# led_board_robot_vs_v2.net
KiCad netlist of a schematic drawn in EAGLE
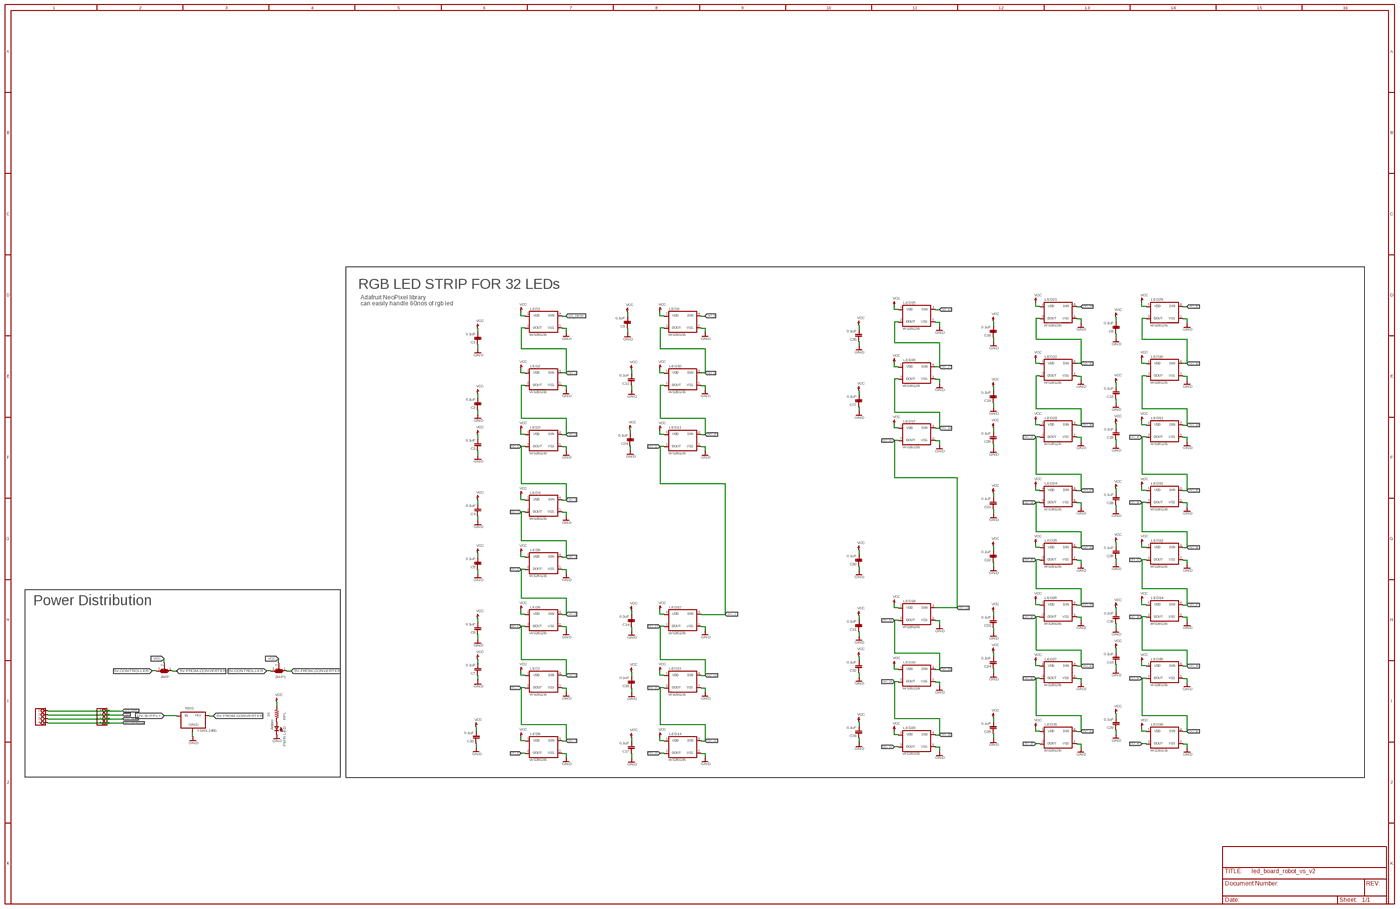
[diagram p0: schematic, sheet 1, overview]
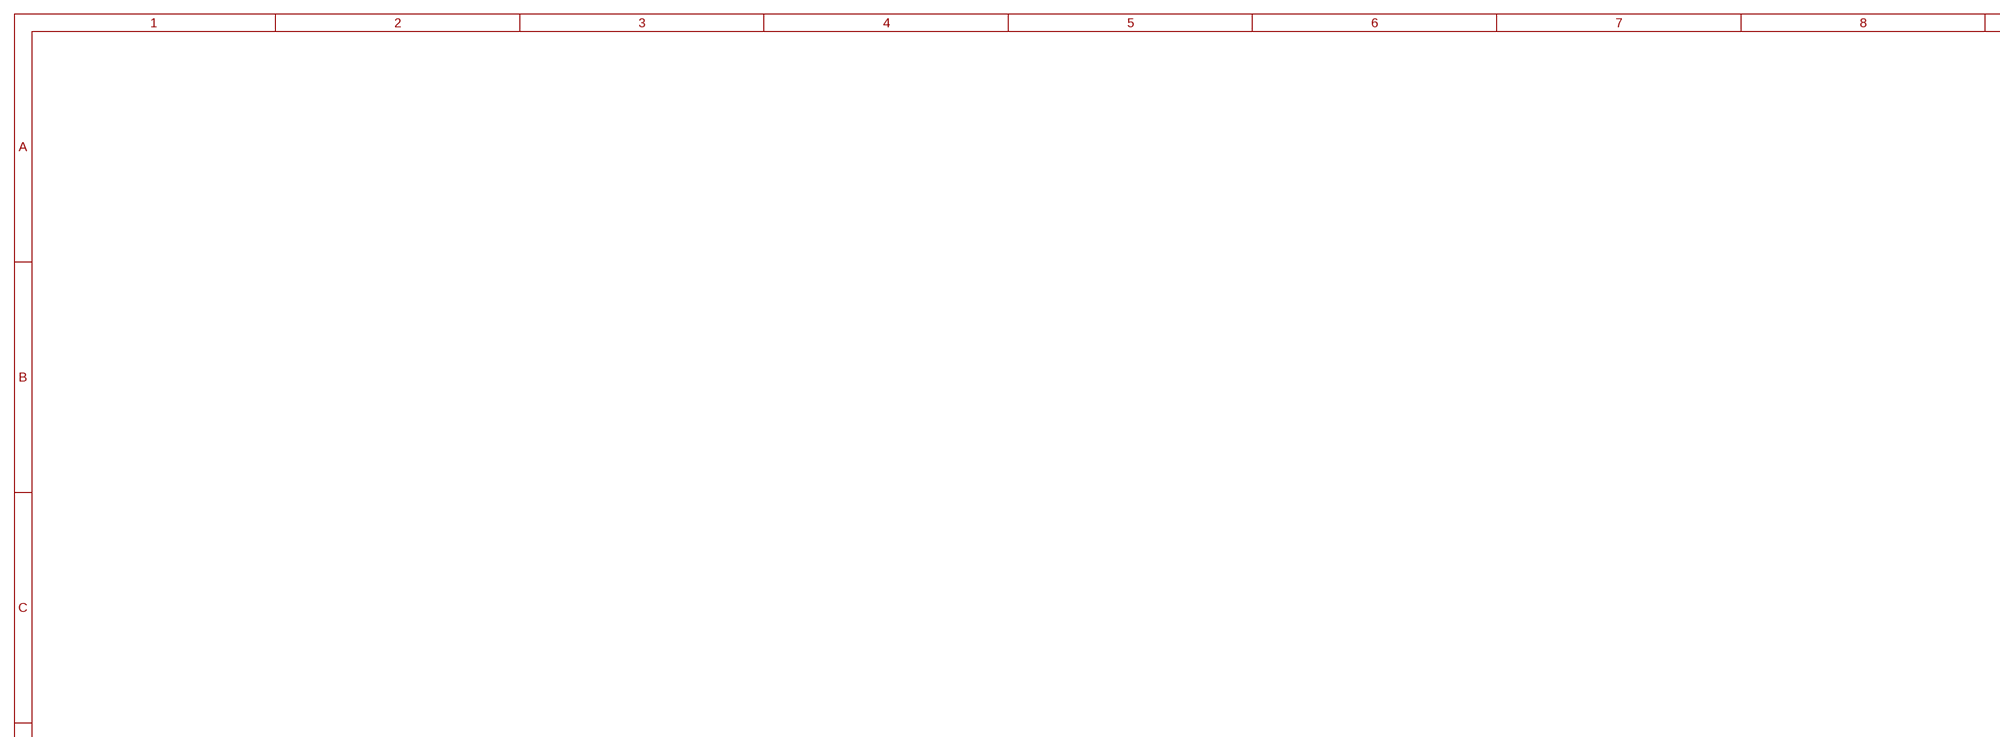
[diagram p1: schematic, sheet 1, part 1 of 4]
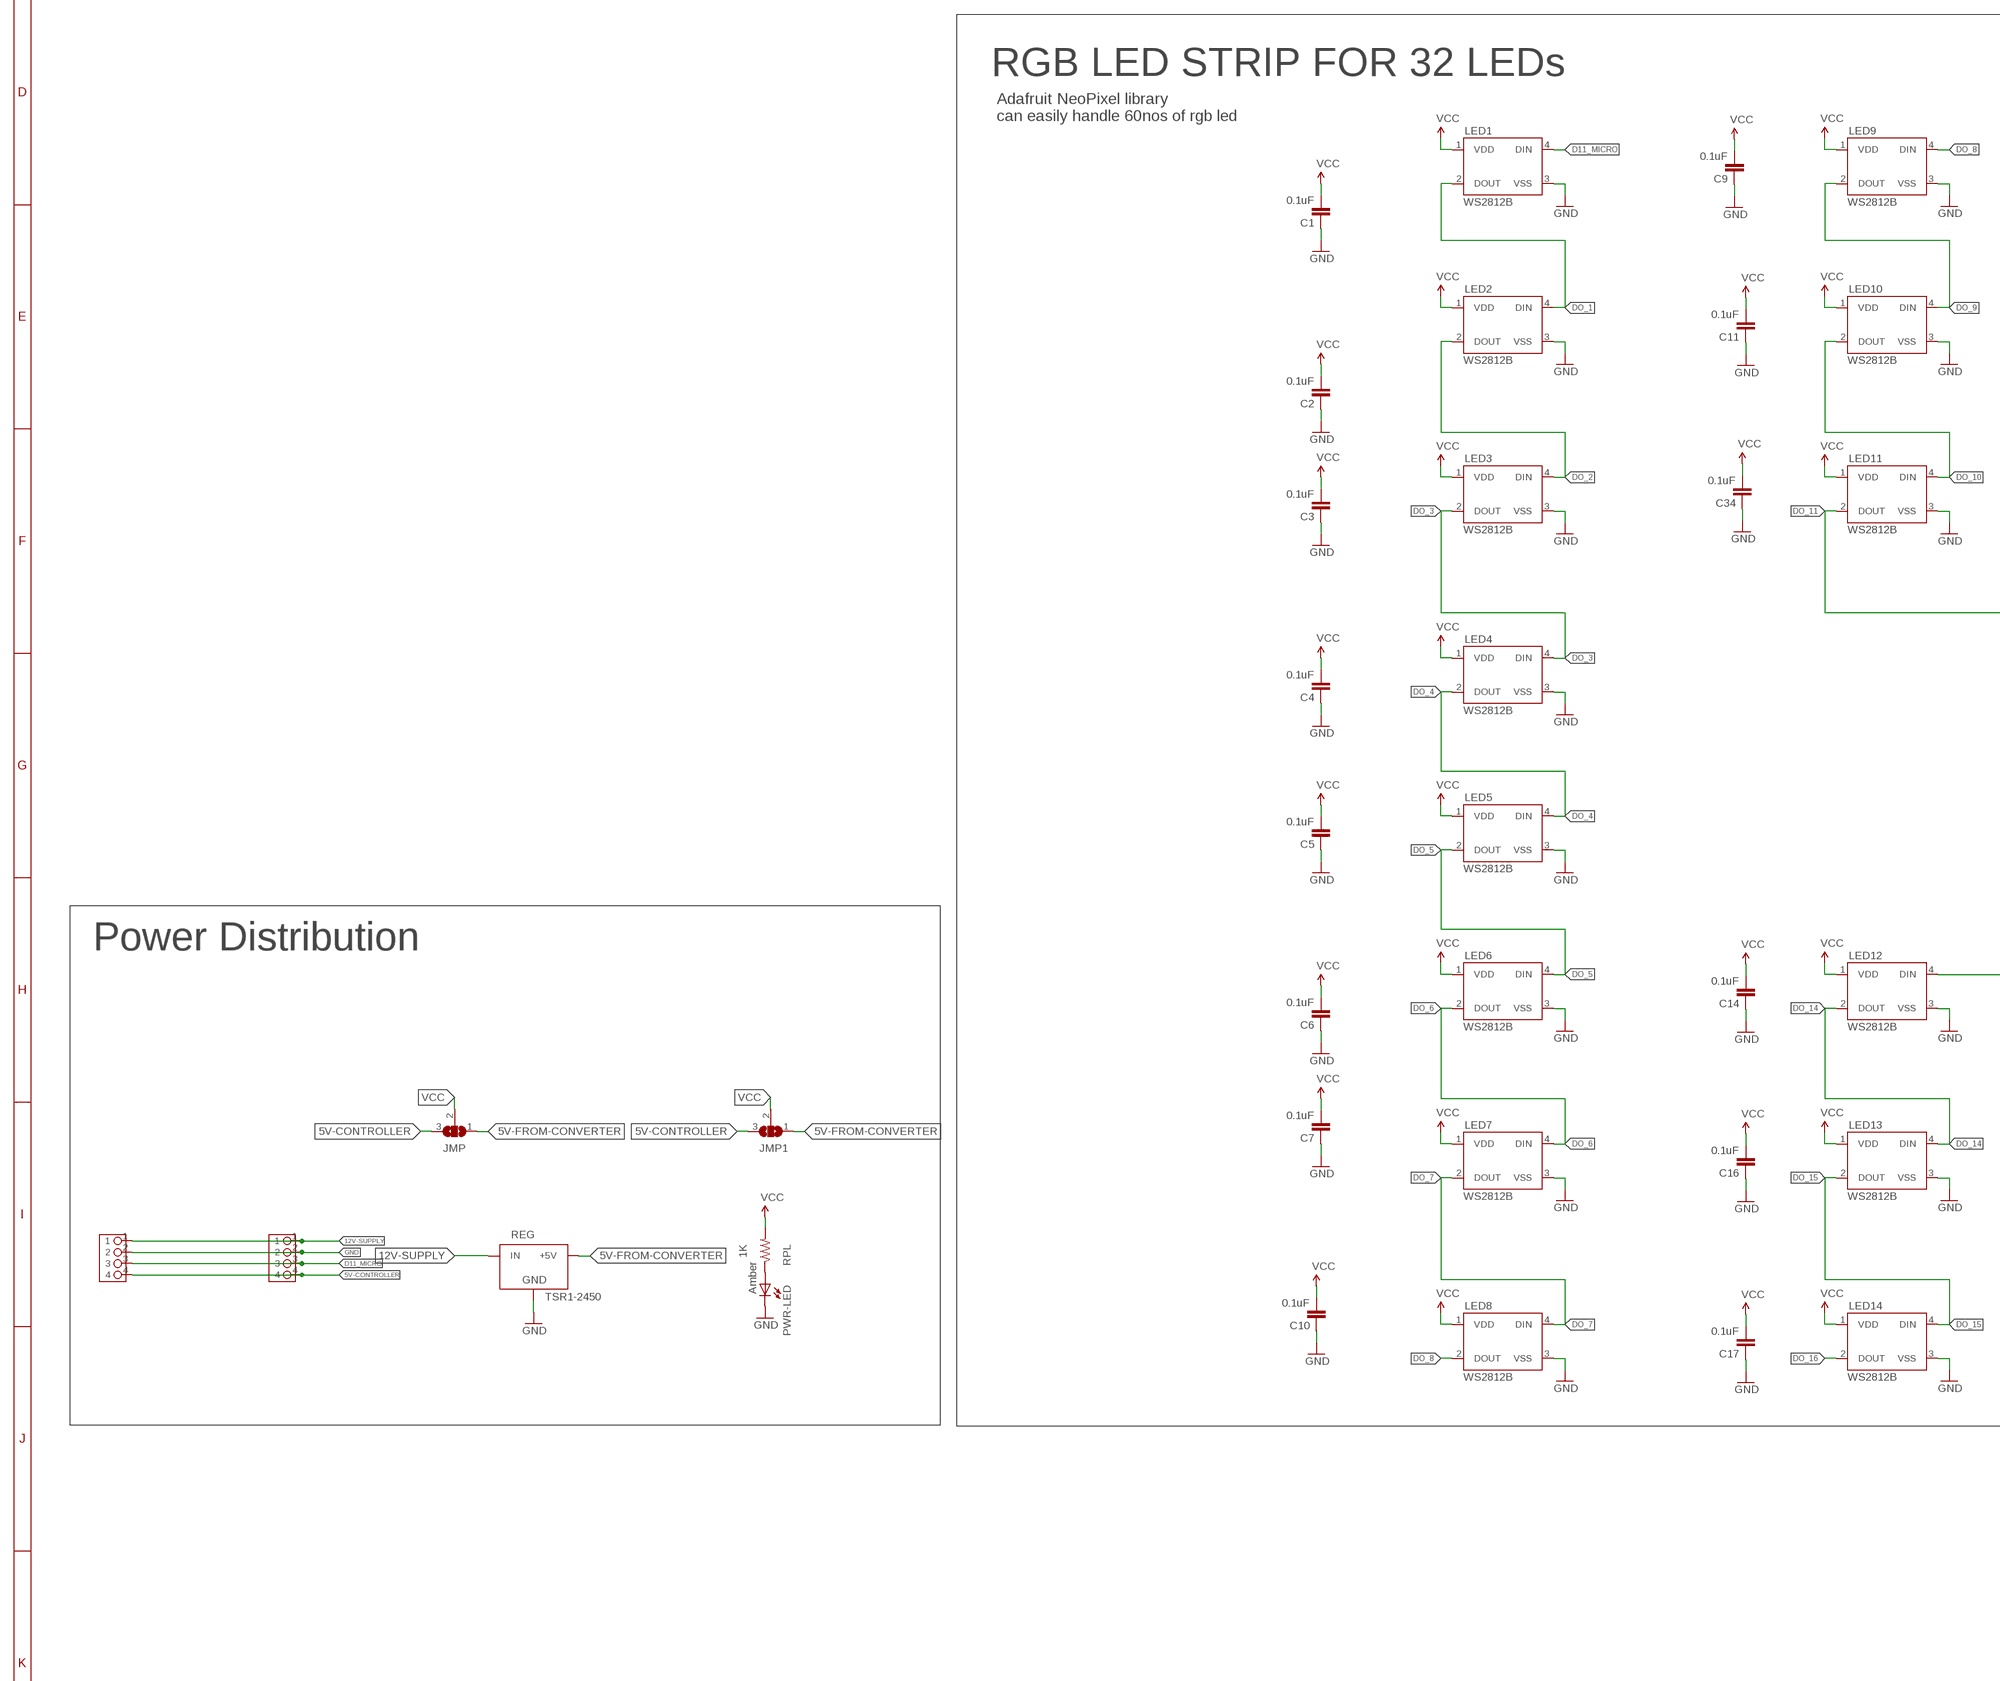
[diagram p2: schematic, sheet 1, part 2 of 4]
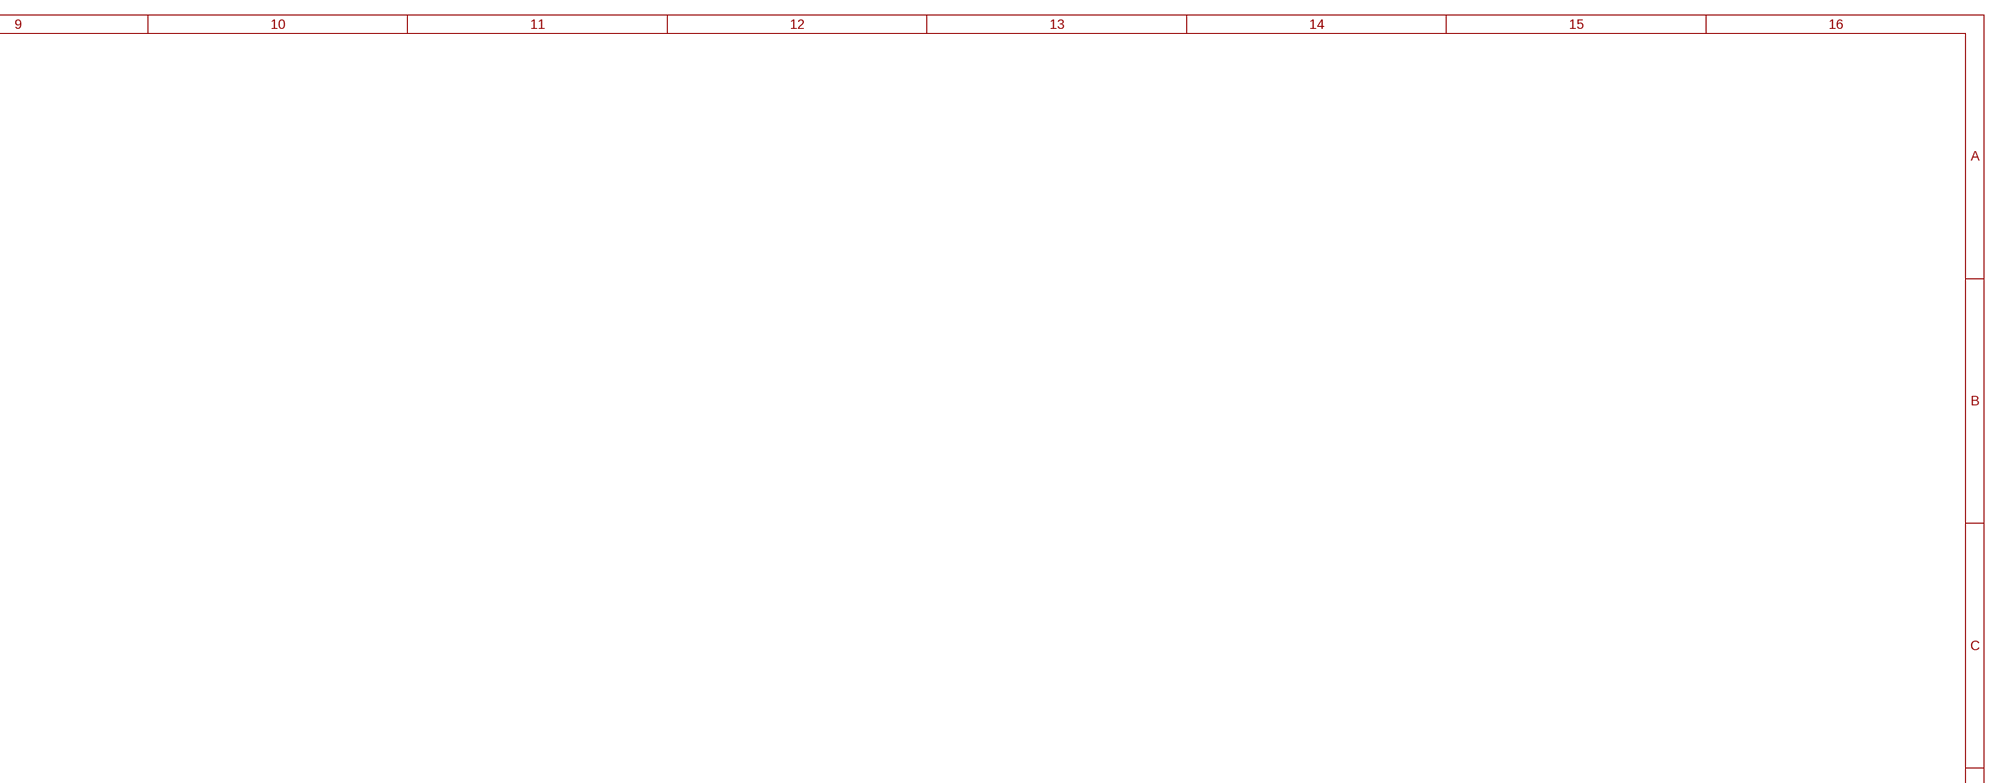
[diagram p3: schematic, sheet 1, part 3 of 4]
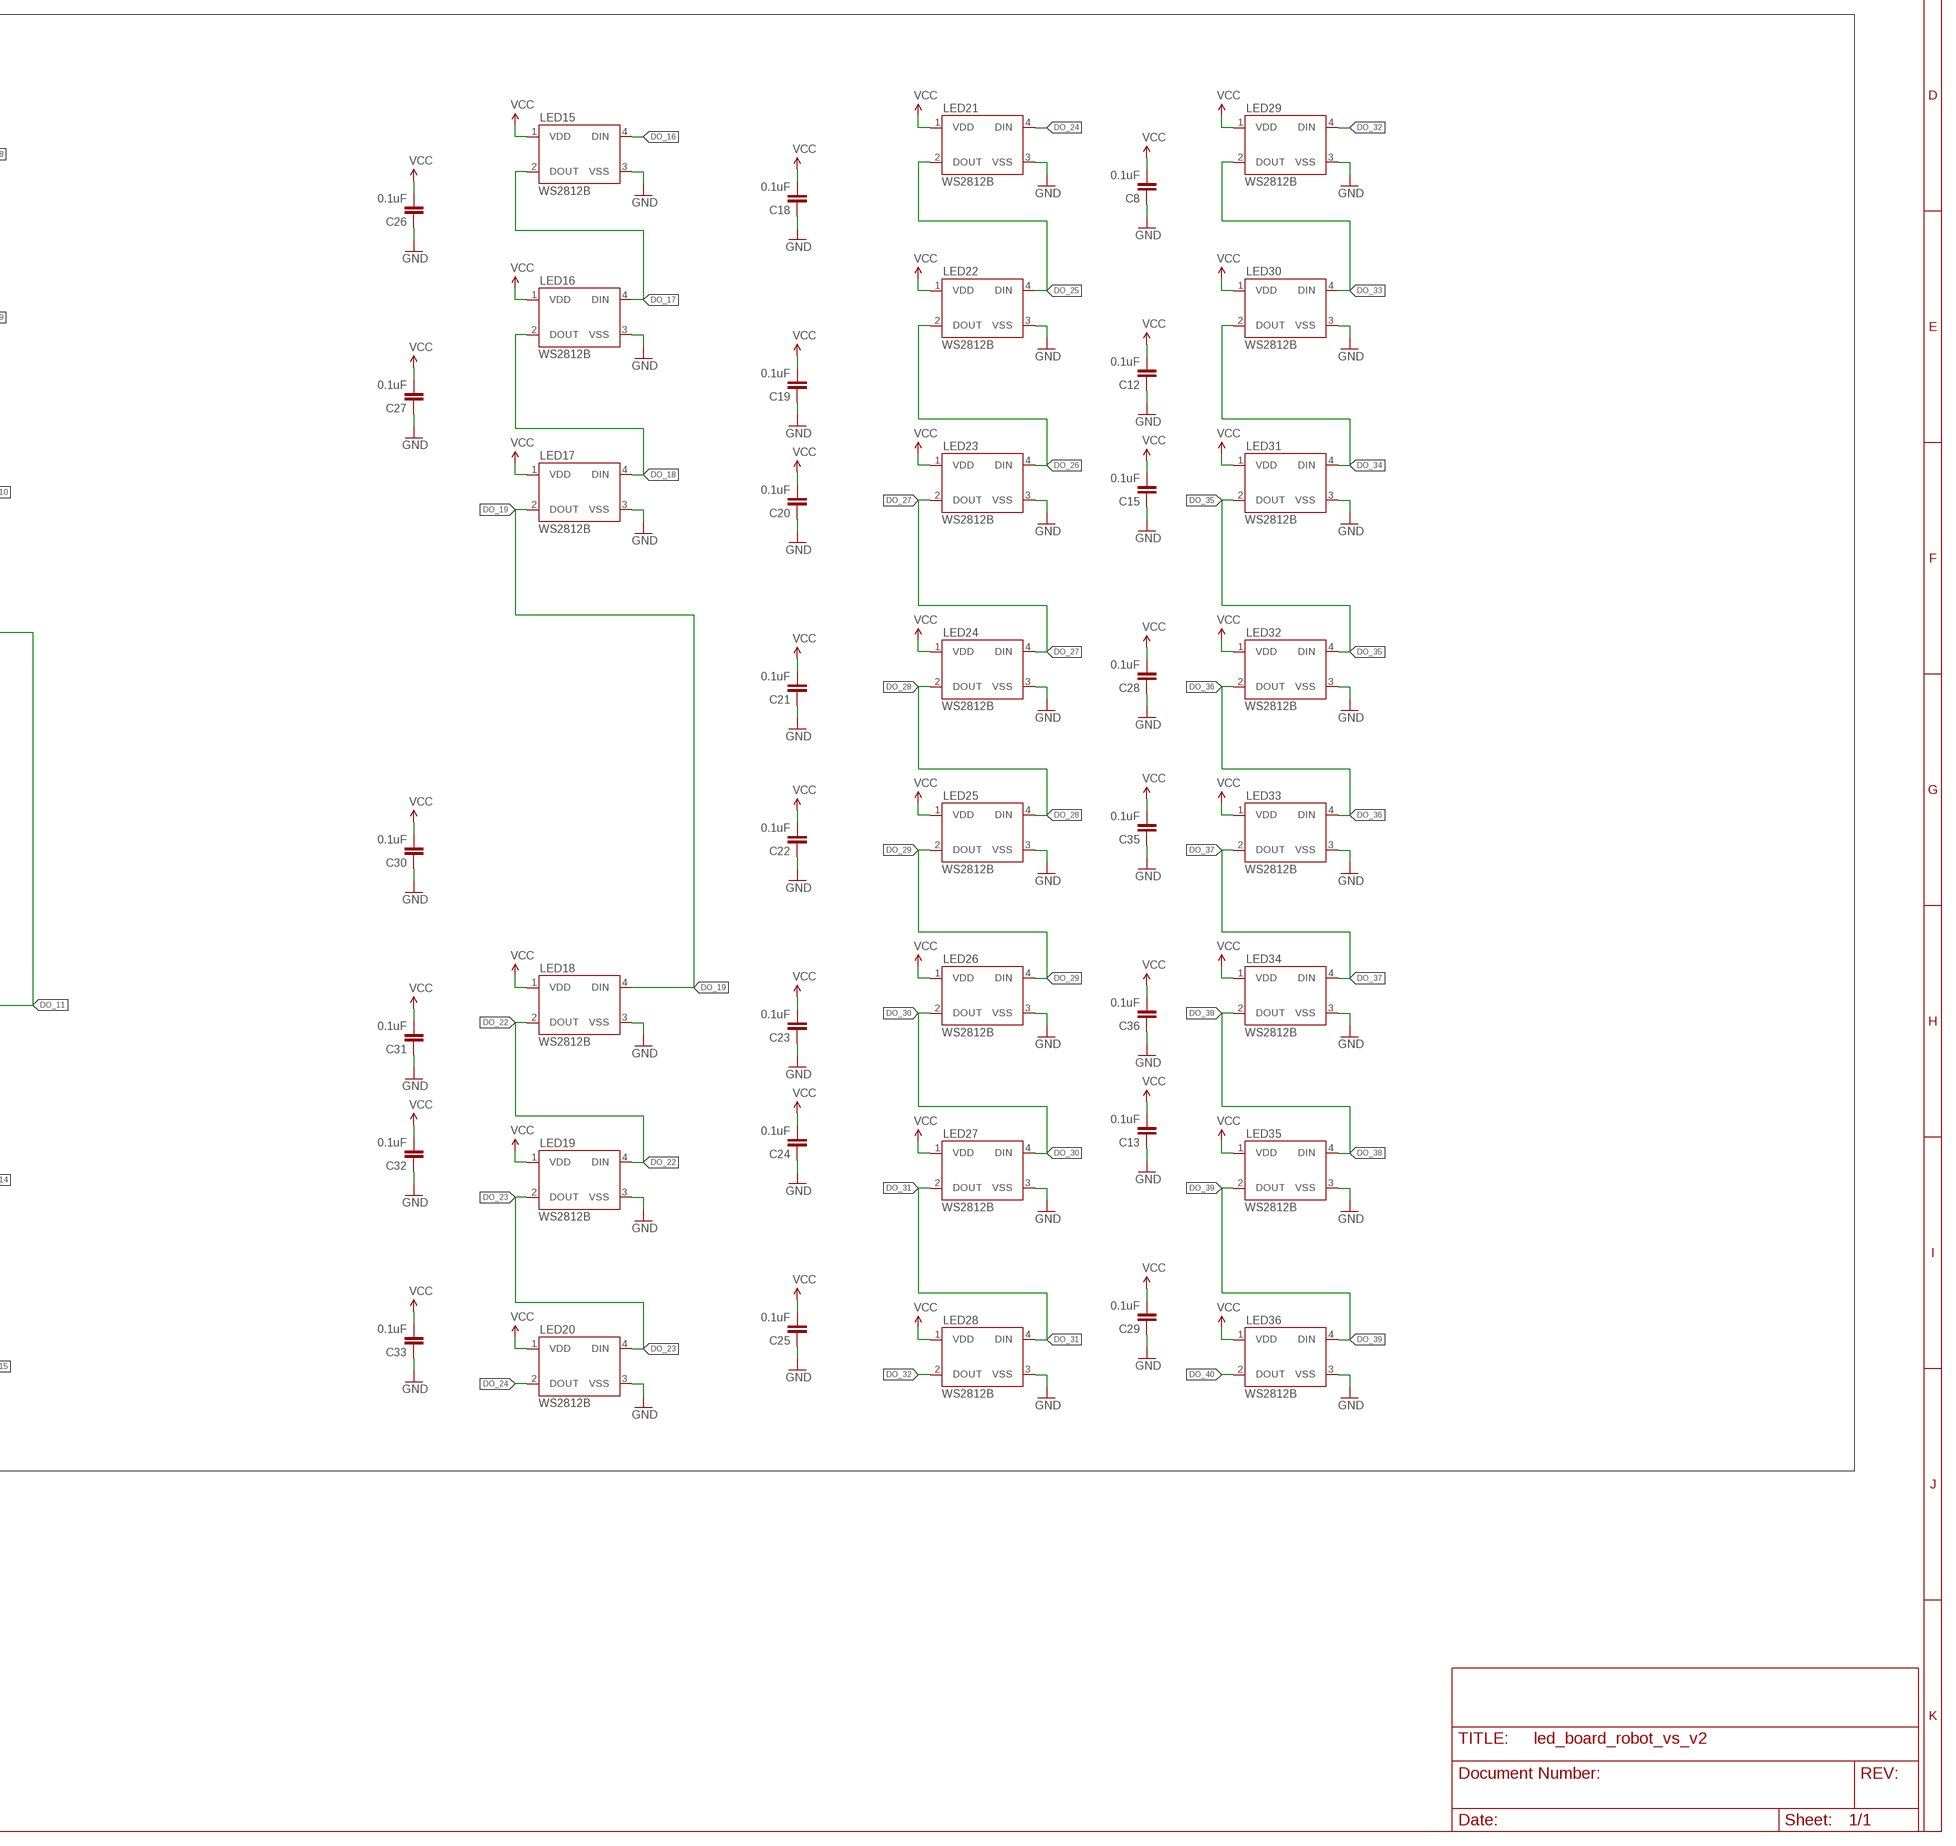
[diagram p4: schematic, sheet 1, part 4 of 4]

(export (version "E")
  (design (tool "Eeschema 10.0.6"))
  (components
    (comp (ref "C1")
      (value "0.1uF")
      (footprint "eagle-import:0603-CAP")
      (libsource (lib "eagle-import") (part "CAP0603-CAP"))
    )
    (comp (ref "C2")
      (value "0.1uF")
      (footprint "eagle-import:0603-CAP")
      (libsource (lib "eagle-import") (part "CAP0603-CAP"))
    )
    (comp (ref "C3")
      (value "0.1uF")
      (footprint "eagle-import:0603-CAP")
      (libsource (lib "eagle-import") (part "CAP0603-CAP"))
    )
    (comp (ref "C4")
      (value "0.1uF")
      (footprint "eagle-import:0603-CAP")
      (libsource (lib "eagle-import") (part "CAP0603-CAP"))
    )
    (comp (ref "C5")
      (value "0.1uF")
      (footprint "eagle-import:0603-CAP")
      (libsource (lib "eagle-import") (part "CAP0603-CAP"))
    )
    (comp (ref "C6")
      (value "0.1uF")
      (footprint "eagle-import:0603-CAP")
      (libsource (lib "eagle-import") (part "CAP0603-CAP"))
    )
    (comp (ref "C7")
      (value "0.1uF")
      (footprint "eagle-import:0603-CAP")
      (libsource (lib "eagle-import") (part "CAP0603-CAP"))
    )
    (comp (ref "C8")
      (value "0.1uF")
      (footprint "eagle-import:0603-CAP")
      (libsource (lib "eagle-import") (part "CAP0603-CAP"))
    )
    (comp (ref "C9")
      (value "0.1uF")
      (footprint "eagle-import:0603-CAP")
      (libsource (lib "eagle-import") (part "CAP0603-CAP"))
    )
    (comp (ref "C10")
      (value "0.1uF")
      (footprint "eagle-import:0603-CAP")
      (libsource (lib "eagle-import") (part "CAP0603-CAP"))
    )
    (comp (ref "C11")
      (value "0.1uF")
      (footprint "eagle-import:0603-CAP")
      (libsource (lib "eagle-import") (part "CAP0603-CAP"))
    )
    (comp (ref "C12")
      (value "0.1uF")
      (footprint "eagle-import:0603-CAP")
      (libsource (lib "eagle-import") (part "CAP0603-CAP"))
    )
    (comp (ref "C13")
      (value "0.1uF")
      (footprint "eagle-import:0603-CAP")
      (libsource (lib "eagle-import") (part "CAP0603-CAP"))
    )
    (comp (ref "C14")
      (value "0.1uF")
      (footprint "eagle-import:0603-CAP")
      (libsource (lib "eagle-import") (part "CAP0603-CAP"))
    )
    (comp (ref "C15")
      (value "0.1uF")
      (footprint "eagle-import:0603-CAP")
      (libsource (lib "eagle-import") (part "CAP0603-CAP"))
    )
    (comp (ref "C16")
      (value "0.1uF")
      (footprint "eagle-import:0603-CAP")
      (libsource (lib "eagle-import") (part "CAP0603-CAP"))
    )
    (comp (ref "C17")
      (value "0.1uF")
      (footprint "eagle-import:0603-CAP")
      (libsource (lib "eagle-import") (part "CAP0603-CAP"))
    )
    (comp (ref "C18")
      (value "0.1uF")
      (footprint "eagle-import:0603-CAP")
      (libsource (lib "eagle-import") (part "CAP0603-CAP"))
    )
    (comp (ref "C19")
      (value "0.1uF")
      (footprint "eagle-import:0603-CAP")
      (libsource (lib "eagle-import") (part "CAP0603-CAP"))
    )
    (comp (ref "C20")
      (value "0.1uF")
      (footprint "eagle-import:0603-CAP")
      (libsource (lib "eagle-import") (part "CAP0603-CAP"))
    )
    (comp (ref "C21")
      (value "0.1uF")
      (footprint "eagle-import:0603-CAP")
      (libsource (lib "eagle-import") (part "CAP0603-CAP"))
    )
    (comp (ref "C22")
      (value "0.1uF")
      (footprint "eagle-import:0603-CAP")
      (libsource (lib "eagle-import") (part "CAP0603-CAP"))
    )
    (comp (ref "C23")
      (value "0.1uF")
      (footprint "eagle-import:0603-CAP")
      (libsource (lib "eagle-import") (part "CAP0603-CAP"))
    )
    (comp (ref "C24")
      (value "0.1uF")
      (footprint "eagle-import:0603-CAP")
      (libsource (lib "eagle-import") (part "CAP0603-CAP"))
    )
    (comp (ref "C25")
      (value "0.1uF")
      (footprint "eagle-import:0603-CAP")
      (libsource (lib "eagle-import") (part "CAP0603-CAP"))
    )
    (comp (ref "C26")
      (value "0.1uF")
      (footprint "eagle-import:0603-CAP")
      (libsource (lib "eagle-import") (part "CAP0603-CAP"))
    )
    (comp (ref "C27")
      (value "0.1uF")
      (footprint "eagle-import:0603-CAP")
      (libsource (lib "eagle-import") (part "CAP0603-CAP"))
    )
    (comp (ref "C28")
      (value "0.1uF")
      (footprint "eagle-import:0603-CAP")
      (libsource (lib "eagle-import") (part "CAP0603-CAP"))
    )
    (comp (ref "C29")
      (value "0.1uF")
      (footprint "eagle-import:0603-CAP")
      (libsource (lib "eagle-import") (part "CAP0603-CAP"))
    )
    (comp (ref "C30")
      (value "0.1uF")
      (footprint "eagle-import:0603-CAP")
      (libsource (lib "eagle-import") (part "CAP0603-CAP"))
    )
    (comp (ref "C31")
      (value "0.1uF")
      (footprint "eagle-import:0603-CAP")
      (libsource (lib "eagle-import") (part "CAP0603-CAP"))
    )
    (comp (ref "C32")
      (value "0.1uF")
      (footprint "eagle-import:0603-CAP")
      (libsource (lib "eagle-import") (part "CAP0603-CAP"))
    )
    (comp (ref "C33")
      (value "0.1uF")
      (footprint "eagle-import:0603-CAP")
      (libsource (lib "eagle-import") (part "CAP0603-CAP"))
    )
    (comp (ref "C34")
      (value "0.1uF")
      (footprint "eagle-import:0603-CAP")
      (libsource (lib "eagle-import") (part "CAP0603-CAP"))
    )
    (comp (ref "C35")
      (value "0.1uF")
      (footprint "eagle-import:0603-CAP")
      (libsource (lib "eagle-import") (part "CAP0603-CAP"))
    )
    (comp (ref "C36")
      (value "0.1uF")
      (footprint "eagle-import:0603-CAP")
      (libsource (lib "eagle-import") (part "CAP0603-CAP"))
    )
    (comp (ref "CON1")
      (value "MOLEX_LOCKING_4PIN")
      (footprint "eagle-import:MOLEX_LOCKING_4PIN")
      (fields (field (name "PARTNO") "43650-0415"))
      (libsource (lib "eagle-import") (part "MOLEX_LOCKING_4PIN"))
    )
    (comp (ref "CON2")
      (value "MOLEX_LOCKING_4PIN")
      (footprint "eagle-import:MOLEX_LOCKING_4PIN")
      (fields (field (name "PARTNO") "43650-0415"))
      (libsource (lib "eagle-import") (part "MOLEX_LOCKING_4PIN"))
    )
    (comp (ref "JMP")
      (value "SJ2WW")
      (footprint "eagle-import:SJ_2W")
      (libsource (lib "eagle-import") (part "SJ2WW"))
    )
    (comp (ref "JMP1")
      (value "SJ2WW")
      (footprint "eagle-import:SJ_2W")
      (libsource (lib "eagle-import") (part "SJ2WW"))
    )
    (comp (ref "LED1")
      (value "WS2812B")
      (footprint "eagle-import:WS2812B")
      (libsource (lib "eagle-import") (part "WS2812B"))
    )
    (comp (ref "LED2")
      (value "WS2812B")
      (footprint "eagle-import:WS2812B")
      (libsource (lib "eagle-import") (part "WS2812B"))
    )
    (comp (ref "LED3")
      (value "WS2812B")
      (footprint "eagle-import:WS2812B")
      (libsource (lib "eagle-import") (part "WS2812B"))
    )
    (comp (ref "LED4")
      (value "WS2812B")
      (footprint "eagle-import:WS2812B")
      (libsource (lib "eagle-import") (part "WS2812B"))
    )
    (comp (ref "LED5")
      (value "WS2812B")
      (footprint "eagle-import:WS2812B")
      (libsource (lib "eagle-import") (part "WS2812B"))
    )
    (comp (ref "LED6")
      (value "WS2812B")
      (footprint "eagle-import:WS2812B")
      (libsource (lib "eagle-import") (part "WS2812B"))
    )
    (comp (ref "LED7")
      (value "WS2812B")
      (footprint "eagle-import:WS2812B")
      (libsource (lib "eagle-import") (part "WS2812B"))
    )
    (comp (ref "LED8")
      (value "WS2812B")
      (footprint "eagle-import:WS2812B")
      (libsource (lib "eagle-import") (part "WS2812B"))
    )
    (comp (ref "LED9")
      (value "WS2812B")
      (footprint "eagle-import:WS2812B")
      (libsource (lib "eagle-import") (part "WS2812B"))
    )
    (comp (ref "LED10")
      (value "WS2812B")
      (footprint "eagle-import:WS2812B")
      (libsource (lib "eagle-import") (part "WS2812B"))
    )
    (comp (ref "LED11")
      (value "WS2812B")
      (footprint "eagle-import:WS2812B")
      (libsource (lib "eagle-import") (part "WS2812B"))
    )
    (comp (ref "LED12")
      (value "WS2812B")
      (footprint "eagle-import:WS2812B")
      (libsource (lib "eagle-import") (part "WS2812B"))
    )
    (comp (ref "LED13")
      (value "WS2812B")
      (footprint "eagle-import:WS2812B")
      (libsource (lib "eagle-import") (part "WS2812B"))
    )
    (comp (ref "LED14")
      (value "WS2812B")
      (footprint "eagle-import:WS2812B")
      (libsource (lib "eagle-import") (part "WS2812B"))
    )
    (comp (ref "LED15")
      (value "WS2812B")
      (footprint "eagle-import:WS2812B")
      (libsource (lib "eagle-import") (part "WS2812B"))
    )
    (comp (ref "LED16")
      (value "WS2812B")
      (footprint "eagle-import:WS2812B")
      (libsource (lib "eagle-import") (part "WS2812B"))
    )
    (comp (ref "LED17")
      (value "WS2812B")
      (footprint "eagle-import:WS2812B")
      (libsource (lib "eagle-import") (part "WS2812B"))
    )
    (comp (ref "LED18")
      (value "WS2812B")
      (footprint "eagle-import:WS2812B")
      (libsource (lib "eagle-import") (part "WS2812B"))
    )
    (comp (ref "LED19")
      (value "WS2812B")
      (footprint "eagle-import:WS2812B")
      (libsource (lib "eagle-import") (part "WS2812B"))
    )
    (comp (ref "LED20")
      (value "WS2812B")
      (footprint "eagle-import:WS2812B")
      (libsource (lib "eagle-import") (part "WS2812B"))
    )
    (comp (ref "LED21")
      (value "WS2812B")
      (footprint "eagle-import:WS2812B")
      (libsource (lib "eagle-import") (part "WS2812B"))
    )
    (comp (ref "LED22")
      (value "WS2812B")
      (footprint "eagle-import:WS2812B")
      (libsource (lib "eagle-import") (part "WS2812B"))
    )
    (comp (ref "LED23")
      (value "WS2812B")
      (footprint "eagle-import:WS2812B")
      (libsource (lib "eagle-import") (part "WS2812B"))
    )
    (comp (ref "LED24")
      (value "WS2812B")
      (footprint "eagle-import:WS2812B")
      (libsource (lib "eagle-import") (part "WS2812B"))
    )
    (comp (ref "LED25")
      (value "WS2812B")
      (footprint "eagle-import:WS2812B")
      (libsource (lib "eagle-import") (part "WS2812B"))
    )
    (comp (ref "LED26")
      (value "WS2812B")
      (footprint "eagle-import:WS2812B")
      (libsource (lib "eagle-import") (part "WS2812B"))
    )
    (comp (ref "LED27")
      (value "WS2812B")
      (footprint "eagle-import:WS2812B")
      (libsource (lib "eagle-import") (part "WS2812B"))
    )
    (comp (ref "LED28")
      (value "WS2812B")
      (footprint "eagle-import:WS2812B")
      (libsource (lib "eagle-import") (part "WS2812B"))
    )
    (comp (ref "LED29")
      (value "WS2812B")
      (footprint "eagle-import:WS2812B")
      (libsource (lib "eagle-import") (part "WS2812B"))
    )
    (comp (ref "LED30")
      (value "WS2812B")
      (footprint "eagle-import:WS2812B")
      (libsource (lib "eagle-import") (part "WS2812B"))
    )
    (comp (ref "LED31")
      (value "WS2812B")
      (footprint "eagle-import:WS2812B")
      (libsource (lib "eagle-import") (part "WS2812B"))
    )
    (comp (ref "LED32")
      (value "WS2812B")
      (footprint "eagle-import:WS2812B")
      (libsource (lib "eagle-import") (part "WS2812B"))
    )
    (comp (ref "LED33")
      (value "WS2812B")
      (footprint "eagle-import:WS2812B")
      (libsource (lib "eagle-import") (part "WS2812B"))
    )
    (comp (ref "LED34")
      (value "WS2812B")
      (footprint "eagle-import:WS2812B")
      (libsource (lib "eagle-import") (part "WS2812B"))
    )
    (comp (ref "LED35")
      (value "WS2812B")
      (footprint "eagle-import:WS2812B")
      (libsource (lib "eagle-import") (part "WS2812B"))
    )
    (comp (ref "LED36")
      (value "WS2812B")
      (footprint "eagle-import:WS2812B")
      (libsource (lib "eagle-import") (part "WS2812B"))
    )
    (comp (ref "PWR-LED")
      (value "Amber")
      (footprint "eagle-import:LED-0603")
      (libsource (lib "eagle-import") (part "LED0603"))
    )
    (comp (ref "REG")
      (value "TSR1-2450")
      (footprint "eagle-import:TSR-1")
      (libsource (lib "eagle-import") (part "TSR1-2450"))
    )
    (comp (ref "RPL")
      (value "1K")
      (footprint "eagle-import:0603-RES")
      (libsource (lib "eagle-import") (part "RESISTOR0603-RES"))
    )
  )
  (nets
    (net (code "1") (name "5V-CONTROLLER") (class "Default")
      (node (ref "CON1") (pin "4") (pinfunction "4_4") (pintype "bidirectional"))
      (node (ref "CON2") (pin "4") (pinfunction "4_4") (pintype "bidirectional"))
      (node (ref "JMP") (pin "3") (pinfunction "3_3") (pintype "passive"))
      (node (ref "JMP1") (pin "3") (pinfunction "3_3") (pintype "passive"))
    )
    (net (code "2") (name "5V-FROM-CONVERTER") (class "Default")
      (node (ref "JMP") (pin "1") (pinfunction "1_1") (pintype "passive"))
      (node (ref "JMP1") (pin "1") (pinfunction "1_1") (pintype "passive"))
      (node (ref "REG") (pin "3") (pinfunction "+5V_3") (pintype "power_in"))
    )
    (net (code "3") (name "12V-SUPPLY") (class "Default")
      (node (ref "CON1") (pin "1") (pinfunction "1_1") (pintype "bidirectional"))
      (node (ref "CON2") (pin "1") (pinfunction "1_1") (pintype "bidirectional"))
      (node (ref "REG") (pin "1") (pinfunction "IN_1") (pintype "power_in"))
    )
    (net (code "4") (name "D11_MICRO") (class "Default")
      (node (ref "CON1") (pin "3") (pinfunction "3_3") (pintype "bidirectional"))
      (node (ref "CON2") (pin "3") (pinfunction "3_3") (pintype "bidirectional"))
      (node (ref "LED1") (pin "4") (pinfunction "DIN_4") (pintype "input"))
    )
    (net (code "5") (name "DO_1") (class "Default")
      (node (ref "LED1") (pin "2") (pinfunction "DOUT_2") (pintype "output"))
      (node (ref "LED2") (pin "4") (pinfunction "DIN_4") (pintype "input"))
    )
    (net (code "6") (name "DO_2") (class "Default")
      (node (ref "LED2") (pin "2") (pinfunction "DOUT_2") (pintype "output"))
      (node (ref "LED3") (pin "4") (pinfunction "DIN_4") (pintype "input"))
    )
    (net (code "7") (name "DO_3") (class "Default")
      (node (ref "LED3") (pin "2") (pinfunction "DOUT_2") (pintype "output"))
      (node (ref "LED4") (pin "4") (pinfunction "DIN_4") (pintype "input"))
    )
    (net (code "8") (name "DO_4") (class "Default")
      (node (ref "LED4") (pin "2") (pinfunction "DOUT_2") (pintype "output"))
      (node (ref "LED5") (pin "4") (pinfunction "DIN_4") (pintype "input"))
    )
    (net (code "9") (name "DO_5") (class "Default")
      (node (ref "LED5") (pin "2") (pinfunction "DOUT_2") (pintype "output"))
      (node (ref "LED6") (pin "4") (pinfunction "DIN_4") (pintype "input"))
    )
    (net (code "10") (name "DO_6") (class "Default")
      (node (ref "LED6") (pin "2") (pinfunction "DOUT_2") (pintype "output"))
      (node (ref "LED7") (pin "4") (pinfunction "DIN_4") (pintype "input"))
    )
    (net (code "11") (name "DO_7") (class "Default")
      (node (ref "LED7") (pin "2") (pinfunction "DOUT_2") (pintype "output"))
      (node (ref "LED8") (pin "4") (pinfunction "DIN_4") (pintype "input"))
    )
    (net (code "12") (name "DO_8") (class "Default")
      (node (ref "LED8") (pin "2") (pinfunction "DOUT_2") (pintype "output"))
      (node (ref "LED9") (pin "4") (pinfunction "DIN_4") (pintype "input"))
    )
    (net (code "13") (name "DO_9") (class "Default")
      (node (ref "LED10") (pin "4") (pinfunction "DIN_4") (pintype "input"))
      (node (ref "LED9") (pin "2") (pinfunction "DOUT_2") (pintype "output"))
    )
    (net (code "14") (name "DO_10") (class "Default")
      (node (ref "LED10") (pin "2") (pinfunction "DOUT_2") (pintype "output"))
      (node (ref "LED11") (pin "4") (pinfunction "DIN_4") (pintype "input"))
    )
    (net (code "15") (name "DO_11") (class "Default")
      (node (ref "LED11") (pin "2") (pinfunction "DOUT_2") (pintype "output"))
      (node (ref "LED12") (pin "4") (pinfunction "DIN_4") (pintype "input"))
    )
    (net (code "16") (name "DO_14") (class "Default")
      (node (ref "LED12") (pin "2") (pinfunction "DOUT_2") (pintype "output"))
      (node (ref "LED13") (pin "4") (pinfunction "DIN_4") (pintype "input"))
    )
    (net (code "17") (name "DO_15") (class "Default")
      (node (ref "LED13") (pin "2") (pinfunction "DOUT_2") (pintype "output"))
      (node (ref "LED14") (pin "4") (pinfunction "DIN_4") (pintype "input"))
    )
    (net (code "18") (name "DO_16") (class "Default")
      (node (ref "LED14") (pin "2") (pinfunction "DOUT_2") (pintype "output"))
      (node (ref "LED15") (pin "4") (pinfunction "DIN_4") (pintype "input"))
    )
    (net (code "19") (name "DO_17") (class "Default")
      (node (ref "LED15") (pin "2") (pinfunction "DOUT_2") (pintype "output"))
      (node (ref "LED16") (pin "4") (pinfunction "DIN_4") (pintype "input"))
    )
    (net (code "20") (name "DO_18") (class "Default")
      (node (ref "LED16") (pin "2") (pinfunction "DOUT_2") (pintype "output"))
      (node (ref "LED17") (pin "4") (pinfunction "DIN_4") (pintype "input"))
    )
    (net (code "21") (name "DO_19") (class "Default")
      (node (ref "LED17") (pin "2") (pinfunction "DOUT_2") (pintype "output"))
      (node (ref "LED18") (pin "4") (pinfunction "DIN_4") (pintype "input"))
    )
    (net (code "22") (name "DO_22") (class "Default")
      (node (ref "LED18") (pin "2") (pinfunction "DOUT_2") (pintype "output"))
      (node (ref "LED19") (pin "4") (pinfunction "DIN_4") (pintype "input"))
    )
    (net (code "23") (name "DO_23") (class "Default")
      (node (ref "LED19") (pin "2") (pinfunction "DOUT_2") (pintype "output"))
      (node (ref "LED20") (pin "4") (pinfunction "DIN_4") (pintype "input"))
    )
    (net (code "24") (name "DO_24") (class "Default")
      (node (ref "LED20") (pin "2") (pinfunction "DOUT_2") (pintype "output"))
      (node (ref "LED21") (pin "4") (pinfunction "DIN_4") (pintype "input"))
    )
    (net (code "25") (name "DO_25") (class "Default")
      (node (ref "LED21") (pin "2") (pinfunction "DOUT_2") (pintype "output"))
      (node (ref "LED22") (pin "4") (pinfunction "DIN_4") (pintype "input"))
    )
    (net (code "26") (name "DO_26") (class "Default")
      (node (ref "LED22") (pin "2") (pinfunction "DOUT_2") (pintype "output"))
      (node (ref "LED23") (pin "4") (pinfunction "DIN_4") (pintype "input"))
    )
    (net (code "27") (name "DO_27") (class "Default")
      (node (ref "LED23") (pin "2") (pinfunction "DOUT_2") (pintype "output"))
      (node (ref "LED24") (pin "4") (pinfunction "DIN_4") (pintype "input"))
    )
    (net (code "28") (name "DO_28") (class "Default")
      (node (ref "LED24") (pin "2") (pinfunction "DOUT_2") (pintype "output"))
      (node (ref "LED25") (pin "4") (pinfunction "DIN_4") (pintype "input"))
    )
    (net (code "29") (name "DO_29") (class "Default")
      (node (ref "LED25") (pin "2") (pinfunction "DOUT_2") (pintype "output"))
      (node (ref "LED26") (pin "4") (pinfunction "DIN_4") (pintype "input"))
    )
    (net (code "30") (name "DO_30") (class "Default")
      (node (ref "LED26") (pin "2") (pinfunction "DOUT_2") (pintype "output"))
      (node (ref "LED27") (pin "4") (pinfunction "DIN_4") (pintype "input"))
    )
    (net (code "31") (name "DO_31") (class "Default")
      (node (ref "LED27") (pin "2") (pinfunction "DOUT_2") (pintype "output"))
      (node (ref "LED28") (pin "4") (pinfunction "DIN_4") (pintype "input"))
    )
    (net (code "32") (name "DO_32") (class "Default")
      (node (ref "LED28") (pin "2") (pinfunction "DOUT_2") (pintype "output"))
      (node (ref "LED29") (pin "4") (pinfunction "DIN_4") (pintype "input"))
    )
    (net (code "33") (name "DO_33") (class "Default")
      (node (ref "LED29") (pin "2") (pinfunction "DOUT_2") (pintype "output"))
      (node (ref "LED30") (pin "4") (pinfunction "DIN_4") (pintype "input"))
    )
    (net (code "34") (name "DO_34") (class "Default")
      (node (ref "LED30") (pin "2") (pinfunction "DOUT_2") (pintype "output"))
      (node (ref "LED31") (pin "4") (pinfunction "DIN_4") (pintype "input"))
    )
    (net (code "35") (name "DO_35") (class "Default")
      (node (ref "LED31") (pin "2") (pinfunction "DOUT_2") (pintype "output"))
      (node (ref "LED32") (pin "4") (pinfunction "DIN_4") (pintype "input"))
    )
    (net (code "36") (name "DO_36") (class "Default")
      (node (ref "LED32") (pin "2") (pinfunction "DOUT_2") (pintype "output"))
      (node (ref "LED33") (pin "4") (pinfunction "DIN_4") (pintype "input"))
    )
    (net (code "37") (name "DO_37") (class "Default")
      (node (ref "LED33") (pin "2") (pinfunction "DOUT_2") (pintype "output"))
      (node (ref "LED34") (pin "4") (pinfunction "DIN_4") (pintype "input"))
    )
    (net (code "38") (name "DO_38") (class "Default")
      (node (ref "LED34") (pin "2") (pinfunction "DOUT_2") (pintype "output"))
      (node (ref "LED35") (pin "4") (pinfunction "DIN_4") (pintype "input"))
    )
    (net (code "39") (name "DO_39") (class "Default")
      (node (ref "LED35") (pin "2") (pinfunction "DOUT_2") (pintype "output"))
      (node (ref "LED36") (pin "4") (pinfunction "DIN_4") (pintype "input"))
    )
    (net (code "40") (name "DO_40") (class "Default")
      (node (ref "LED36") (pin "2") (pinfunction "DOUT_2") (pintype "output"))
    )
    (net (code "41") (name "GND") (class "Default")
      (node (ref "C1") (pin "1") (pinfunction "1_1") (pintype "passive"))
      (node (ref "C10") (pin "1") (pinfunction "1_1") (pintype "passive"))
      (node (ref "C11") (pin "1") (pinfunction "1_1") (pintype "passive"))
      (node (ref "C12") (pin "1") (pinfunction "1_1") (pintype "passive"))
      (node (ref "C13") (pin "1") (pinfunction "1_1") (pintype "passive"))
      (node (ref "C14") (pin "1") (pinfunction "1_1") (pintype "passive"))
      (node (ref "C15") (pin "1") (pinfunction "1_1") (pintype "passive"))
      (node (ref "C16") (pin "1") (pinfunction "1_1") (pintype "passive"))
      (node (ref "C17") (pin "1") (pinfunction "1_1") (pintype "passive"))
      (node (ref "C18") (pin "1") (pinfunction "1_1") (pintype "passive"))
      (node (ref "C19") (pin "1") (pinfunction "1_1") (pintype "passive"))
      (node (ref "C2") (pin "1") (pinfunction "1_1") (pintype "passive"))
      (node (ref "C20") (pin "1") (pinfunction "1_1") (pintype "passive"))
      (node (ref "C21") (pin "1") (pinfunction "1_1") (pintype "passive"))
      (node (ref "C22") (pin "1") (pinfunction "1_1") (pintype "passive"))
      (node (ref "C23") (pin "1") (pinfunction "1_1") (pintype "passive"))
      (node (ref "C24") (pin "1") (pinfunction "1_1") (pintype "passive"))
      (node (ref "C25") (pin "1") (pinfunction "1_1") (pintype "passive"))
      (node (ref "C26") (pin "1") (pinfunction "1_1") (pintype "passive"))
      (node (ref "C27") (pin "1") (pinfunction "1_1") (pintype "passive"))
      (node (ref "C28") (pin "1") (pinfunction "1_1") (pintype "passive"))
      (node (ref "C29") (pin "1") (pinfunction "1_1") (pintype "passive"))
      (node (ref "C3") (pin "1") (pinfunction "1_1") (pintype "passive"))
      (node (ref "C30") (pin "1") (pinfunction "1_1") (pintype "passive"))
      (node (ref "C31") (pin "1") (pinfunction "1_1") (pintype "passive"))
      (node (ref "C32") (pin "1") (pinfunction "1_1") (pintype "passive"))
      (node (ref "C33") (pin "1") (pinfunction "1_1") (pintype "passive"))
      (node (ref "C34") (pin "1") (pinfunction "1_1") (pintype "passive"))
      (node (ref "C35") (pin "1") (pinfunction "1_1") (pintype "passive"))
      (node (ref "C36") (pin "1") (pinfunction "1_1") (pintype "passive"))
      (node (ref "C4") (pin "1") (pinfunction "1_1") (pintype "passive"))
      (node (ref "C5") (pin "1") (pinfunction "1_1") (pintype "passive"))
      (node (ref "C6") (pin "1") (pinfunction "1_1") (pintype "passive"))
      (node (ref "C7") (pin "1") (pinfunction "1_1") (pintype "passive"))
      (node (ref "C8") (pin "1") (pinfunction "1_1") (pintype "passive"))
      (node (ref "C9") (pin "1") (pinfunction "1_1") (pintype "passive"))
      (node (ref "CON1") (pin "2") (pinfunction "2_2") (pintype "bidirectional"))
      (node (ref "CON2") (pin "2") (pinfunction "2_2") (pintype "bidirectional"))
      (node (ref "LED1") (pin "3") (pinfunction "VSS_3") (pintype "power_in"))
      (node (ref "LED10") (pin "3") (pinfunction "VSS_3") (pintype "power_in"))
      (node (ref "LED11") (pin "3") (pinfunction "VSS_3") (pintype "power_in"))
      (node (ref "LED12") (pin "3") (pinfunction "VSS_3") (pintype "power_in"))
      (node (ref "LED13") (pin "3") (pinfunction "VSS_3") (pintype "power_in"))
      (node (ref "LED14") (pin "3") (pinfunction "VSS_3") (pintype "power_in"))
      (node (ref "LED15") (pin "3") (pinfunction "VSS_3") (pintype "power_in"))
      (node (ref "LED16") (pin "3") (pinfunction "VSS_3") (pintype "power_in"))
      (node (ref "LED17") (pin "3") (pinfunction "VSS_3") (pintype "power_in"))
      (node (ref "LED18") (pin "3") (pinfunction "VSS_3") (pintype "power_in"))
      (node (ref "LED19") (pin "3") (pinfunction "VSS_3") (pintype "power_in"))
      (node (ref "LED2") (pin "3") (pinfunction "VSS_3") (pintype "power_in"))
      (node (ref "LED20") (pin "3") (pinfunction "VSS_3") (pintype "power_in"))
      (node (ref "LED21") (pin "3") (pinfunction "VSS_3") (pintype "power_in"))
      (node (ref "LED22") (pin "3") (pinfunction "VSS_3") (pintype "power_in"))
      (node (ref "LED23") (pin "3") (pinfunction "VSS_3") (pintype "power_in"))
      (node (ref "LED24") (pin "3") (pinfunction "VSS_3") (pintype "power_in"))
      (node (ref "LED25") (pin "3") (pinfunction "VSS_3") (pintype "power_in"))
      (node (ref "LED26") (pin "3") (pinfunction "VSS_3") (pintype "power_in"))
      (node (ref "LED27") (pin "3") (pinfunction "VSS_3") (pintype "power_in"))
      (node (ref "LED28") (pin "3") (pinfunction "VSS_3") (pintype "power_in"))
      (node (ref "LED29") (pin "3") (pinfunction "VSS_3") (pintype "power_in"))
      (node (ref "LED3") (pin "3") (pinfunction "VSS_3") (pintype "power_in"))
      (node (ref "LED30") (pin "3") (pinfunction "VSS_3") (pintype "power_in"))
      (node (ref "LED31") (pin "3") (pinfunction "VSS_3") (pintype "power_in"))
      (node (ref "LED32") (pin "3") (pinfunction "VSS_3") (pintype "power_in"))
      (node (ref "LED33") (pin "3") (pinfunction "VSS_3") (pintype "power_in"))
      (node (ref "LED34") (pin "3") (pinfunction "VSS_3") (pintype "power_in"))
      (node (ref "LED35") (pin "3") (pinfunction "VSS_3") (pintype "power_in"))
      (node (ref "LED36") (pin "3") (pinfunction "VSS_3") (pintype "power_in"))
      (node (ref "LED4") (pin "3") (pinfunction "VSS_3") (pintype "power_in"))
      (node (ref "LED5") (pin "3") (pinfunction "VSS_3") (pintype "power_in"))
      (node (ref "LED6") (pin "3") (pinfunction "VSS_3") (pintype "power_in"))
      (node (ref "LED7") (pin "3") (pinfunction "VSS_3") (pintype "power_in"))
      (node (ref "LED8") (pin "3") (pinfunction "VSS_3") (pintype "power_in"))
      (node (ref "LED9") (pin "3") (pinfunction "VSS_3") (pintype "power_in"))
      (node (ref "PWR-LED") (pin "C") (pinfunction "C_C") (pintype "passive"))
      (node (ref "REG") (pin "2") (pinfunction "GND_2") (pintype "power_in"))
    )
    (net (code "42") (name "Net-(PWR-LED-PadA)") (class "Default")
      (node (ref "PWR-LED") (pin "A") (pinfunction "A_A") (pintype "passive"))
      (node (ref "RPL") (pin "1") (pinfunction "1_1") (pintype "passive"))
    )
    (net (code "43") (name "VCC") (class "Default")
      (node (ref "C1") (pin "2") (pinfunction "2_2") (pintype "passive"))
      (node (ref "C10") (pin "2") (pinfunction "2_2") (pintype "passive"))
      (node (ref "C11") (pin "2") (pinfunction "2_2") (pintype "passive"))
      (node (ref "C12") (pin "2") (pinfunction "2_2") (pintype "passive"))
      (node (ref "C13") (pin "2") (pinfunction "2_2") (pintype "passive"))
      (node (ref "C14") (pin "2") (pinfunction "2_2") (pintype "passive"))
      (node (ref "C15") (pin "2") (pinfunction "2_2") (pintype "passive"))
      (node (ref "C16") (pin "2") (pinfunction "2_2") (pintype "passive"))
      (node (ref "C17") (pin "2") (pinfunction "2_2") (pintype "passive"))
      (node (ref "C18") (pin "2") (pinfunction "2_2") (pintype "passive"))
      (node (ref "C19") (pin "2") (pinfunction "2_2") (pintype "passive"))
      (node (ref "C2") (pin "2") (pinfunction "2_2") (pintype "passive"))
      (node (ref "C20") (pin "2") (pinfunction "2_2") (pintype "passive"))
      (node (ref "C21") (pin "2") (pinfunction "2_2") (pintype "passive"))
      (node (ref "C22") (pin "2") (pinfunction "2_2") (pintype "passive"))
      (node (ref "C23") (pin "2") (pinfunction "2_2") (pintype "passive"))
      (node (ref "C24") (pin "2") (pinfunction "2_2") (pintype "passive"))
      (node (ref "C25") (pin "2") (pinfunction "2_2") (pintype "passive"))
      (node (ref "C26") (pin "2") (pinfunction "2_2") (pintype "passive"))
      (node (ref "C27") (pin "2") (pinfunction "2_2") (pintype "passive"))
      (node (ref "C28") (pin "2") (pinfunction "2_2") (pintype "passive"))
      (node (ref "C29") (pin "2") (pinfunction "2_2") (pintype "passive"))
      (node (ref "C3") (pin "2") (pinfunction "2_2") (pintype "passive"))
      (node (ref "C30") (pin "2") (pinfunction "2_2") (pintype "passive"))
      (node (ref "C31") (pin "2") (pinfunction "2_2") (pintype "passive"))
      (node (ref "C32") (pin "2") (pinfunction "2_2") (pintype "passive"))
      (node (ref "C33") (pin "2") (pinfunction "2_2") (pintype "passive"))
      (node (ref "C34") (pin "2") (pinfunction "2_2") (pintype "passive"))
      (node (ref "C35") (pin "2") (pinfunction "2_2") (pintype "passive"))
      (node (ref "C36") (pin "2") (pinfunction "2_2") (pintype "passive"))
      (node (ref "C4") (pin "2") (pinfunction "2_2") (pintype "passive"))
      (node (ref "C5") (pin "2") (pinfunction "2_2") (pintype "passive"))
      (node (ref "C6") (pin "2") (pinfunction "2_2") (pintype "passive"))
      (node (ref "C7") (pin "2") (pinfunction "2_2") (pintype "passive"))
      (node (ref "C8") (pin "2") (pinfunction "2_2") (pintype "passive"))
      (node (ref "C9") (pin "2") (pinfunction "2_2") (pintype "passive"))
      (node (ref "JMP") (pin "2") (pinfunction "2_2") (pintype "passive"))
      (node (ref "JMP1") (pin "2") (pinfunction "2_2") (pintype "passive"))
      (node (ref "LED1") (pin "1") (pinfunction "VDD_1") (pintype "power_in"))
      (node (ref "LED10") (pin "1") (pinfunction "VDD_1") (pintype "power_in"))
      (node (ref "LED11") (pin "1") (pinfunction "VDD_1") (pintype "power_in"))
      (node (ref "LED12") (pin "1") (pinfunction "VDD_1") (pintype "power_in"))
      (node (ref "LED13") (pin "1") (pinfunction "VDD_1") (pintype "power_in"))
      (node (ref "LED14") (pin "1") (pinfunction "VDD_1") (pintype "power_in"))
      (node (ref "LED15") (pin "1") (pinfunction "VDD_1") (pintype "power_in"))
      (node (ref "LED16") (pin "1") (pinfunction "VDD_1") (pintype "power_in"))
      (node (ref "LED17") (pin "1") (pinfunction "VDD_1") (pintype "power_in"))
      (node (ref "LED18") (pin "1") (pinfunction "VDD_1") (pintype "power_in"))
      (node (ref "LED19") (pin "1") (pinfunction "VDD_1") (pintype "power_in"))
      (node (ref "LED2") (pin "1") (pinfunction "VDD_1") (pintype "power_in"))
      (node (ref "LED20") (pin "1") (pinfunction "VDD_1") (pintype "power_in"))
      (node (ref "LED21") (pin "1") (pinfunction "VDD_1") (pintype "power_in"))
      (node (ref "LED22") (pin "1") (pinfunction "VDD_1") (pintype "power_in"))
      (node (ref "LED23") (pin "1") (pinfunction "VDD_1") (pintype "power_in"))
      (node (ref "LED24") (pin "1") (pinfunction "VDD_1") (pintype "power_in"))
      (node (ref "LED25") (pin "1") (pinfunction "VDD_1") (pintype "power_in"))
      (node (ref "LED26") (pin "1") (pinfunction "VDD_1") (pintype "power_in"))
      (node (ref "LED27") (pin "1") (pinfunction "VDD_1") (pintype "power_in"))
      (node (ref "LED28") (pin "1") (pinfunction "VDD_1") (pintype "power_in"))
      (node (ref "LED29") (pin "1") (pinfunction "VDD_1") (pintype "power_in"))
      (node (ref "LED3") (pin "1") (pinfunction "VDD_1") (pintype "power_in"))
      (node (ref "LED30") (pin "1") (pinfunction "VDD_1") (pintype "power_in"))
      (node (ref "LED31") (pin "1") (pinfunction "VDD_1") (pintype "power_in"))
      (node (ref "LED32") (pin "1") (pinfunction "VDD_1") (pintype "power_in"))
      (node (ref "LED33") (pin "1") (pinfunction "VDD_1") (pintype "power_in"))
      (node (ref "LED34") (pin "1") (pinfunction "VDD_1") (pintype "power_in"))
      (node (ref "LED35") (pin "1") (pinfunction "VDD_1") (pintype "power_in"))
      (node (ref "LED36") (pin "1") (pinfunction "VDD_1") (pintype "power_in"))
      (node (ref "LED4") (pin "1") (pinfunction "VDD_1") (pintype "power_in"))
      (node (ref "LED5") (pin "1") (pinfunction "VDD_1") (pintype "power_in"))
      (node (ref "LED6") (pin "1") (pinfunction "VDD_1") (pintype "power_in"))
      (node (ref "LED7") (pin "1") (pinfunction "VDD_1") (pintype "power_in"))
      (node (ref "LED8") (pin "1") (pinfunction "VDD_1") (pintype "power_in"))
      (node (ref "LED9") (pin "1") (pinfunction "VDD_1") (pintype "power_in"))
      (node (ref "RPL") (pin "2") (pinfunction "2_2") (pintype "passive"))
    )
  )
)
